# Sheet1.net
KiCad netlist of a schematic drawn in Altium Designer
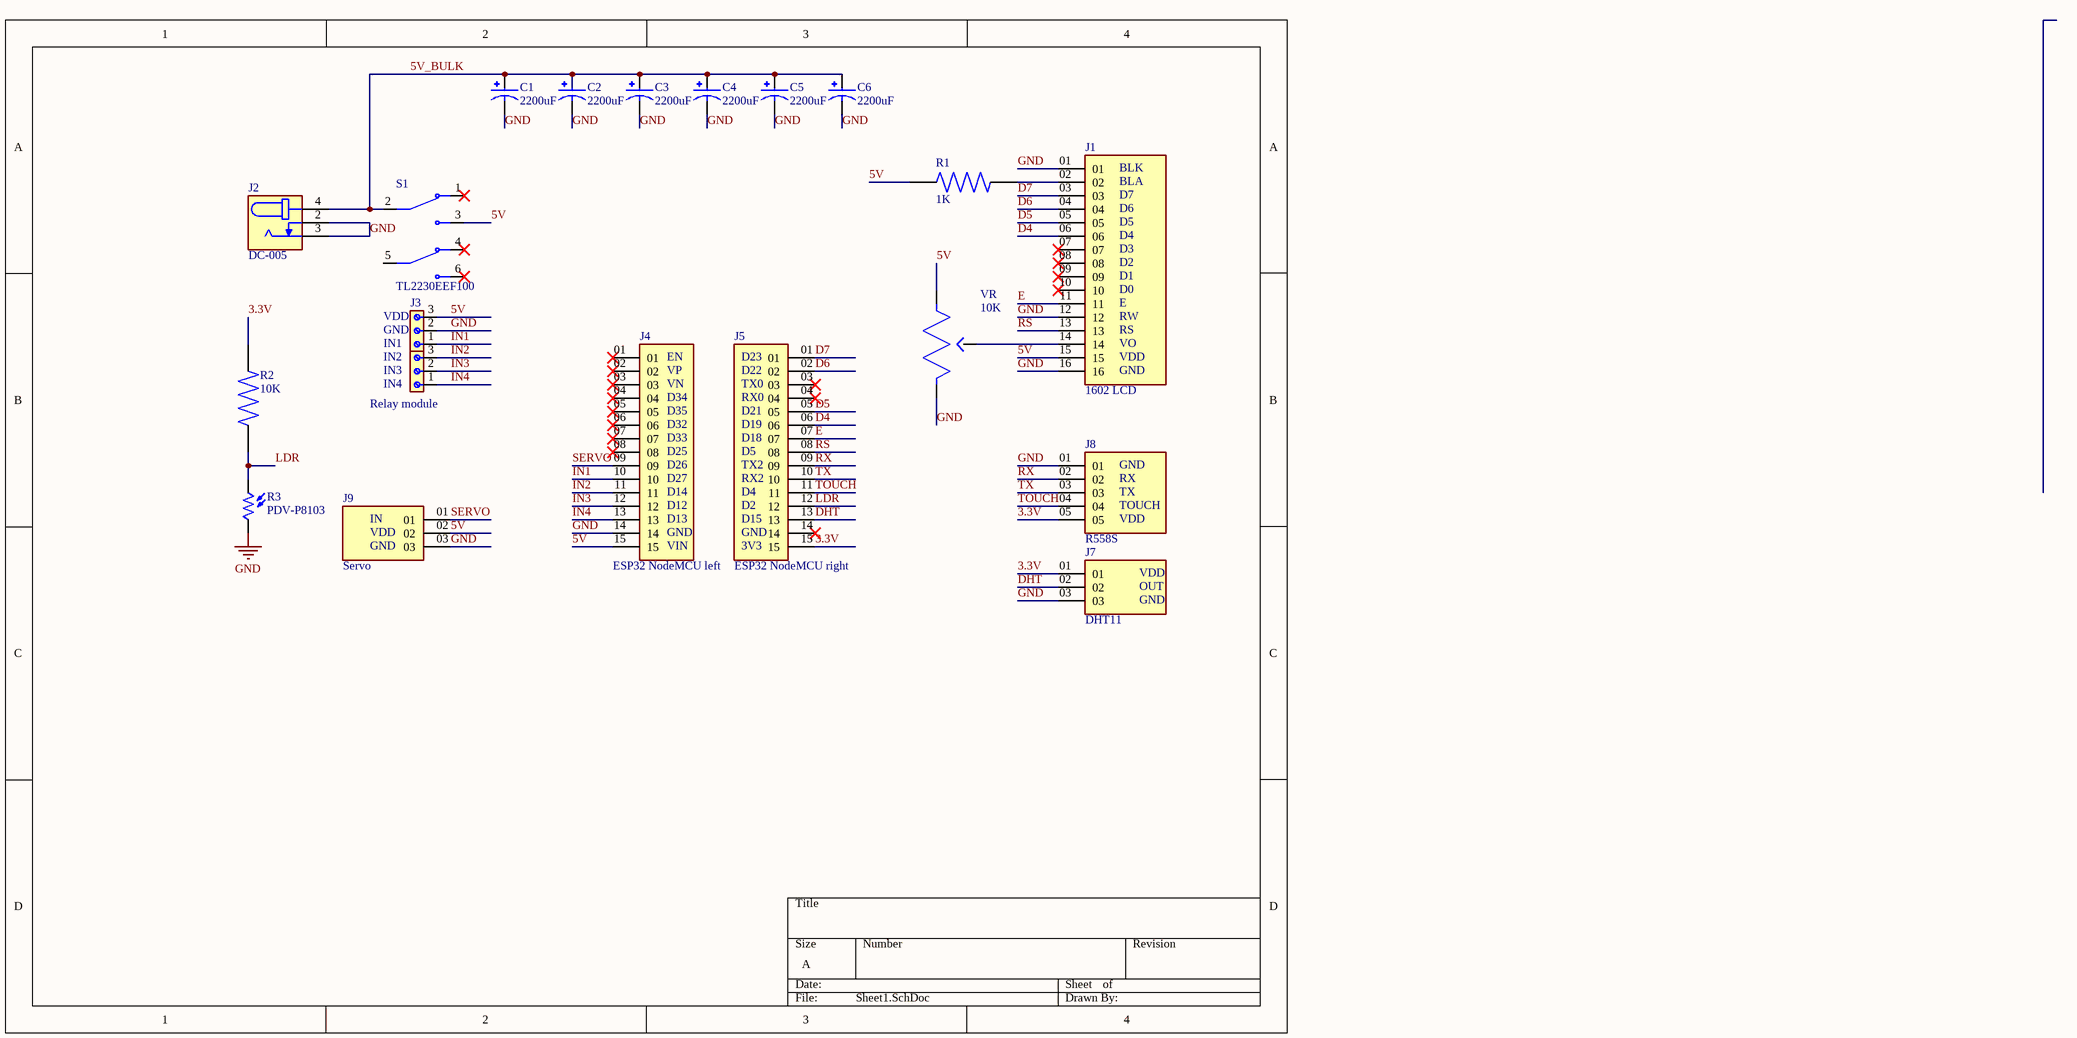
[diagram p0: Sheet1.SchDoc]

(export (version "E")
  (design (tool "Eeschema 10.0.6"))
  (components
    (comp (ref "C1")
      (value "2200uF")
      (footprint "CAPPRD500W60D1250H2000")
      (description "Cap Aluminum Lytic 2200uF 16V 20% (12.5 X 20mm) Radial 5mm 2600mA 10000h 105C Bulk")
      (fields (field (name "MP") "EEUFR1C222") (field (name "MF") "Panasonic"))
      (libsource (lib "EEUFR1C222") (part "EEUFR1C222"))
    )
    (comp (ref "C2")
      (value "2200uF")
      (footprint "CAPPRD500W60D1250H2000")
      (description "Cap Aluminum Lytic 2200uF 16V 20% (12.5 X 20mm) Radial 5mm 2600mA 10000h 105C Bulk")
      (fields (field (name "MP") "EEUFR1C222") (field (name "MF") "Panasonic"))
      (libsource (lib "EEUFR1C222") (part "EEUFR1C222"))
    )
    (comp (ref "C3")
      (value "2200uF")
      (footprint "CAPPRD500W60D1250H2000")
      (description "Cap Aluminum Lytic 2200uF 16V 20% (12.5 X 20mm) Radial 5mm 2600mA 10000h 105C Bulk")
      (fields (field (name "MP") "EEUFR1C222") (field (name "MF") "Panasonic"))
      (libsource (lib "EEUFR1C222") (part "EEUFR1C222"))
    )
    (comp (ref "C4")
      (value "2200uF")
      (footprint "CAPPRD500W60D1250H2000")
      (description "Cap Aluminum Lytic 2200uF 16V 20% (12.5 X 20mm) Radial 5mm 2600mA 10000h 105C Bulk")
      (fields (field (name "MP") "EEUFR1C222") (field (name "MF") "Panasonic"))
      (libsource (lib "EEUFR1C222") (part "EEUFR1C222"))
    )
    (comp (ref "C5")
      (value "2200uF")
      (footprint "CAPPRD500W60D1250H2000")
      (description "Cap Aluminum Lytic 2200uF 16V 20% (12.5 X 20mm) Radial 5mm 2600mA 10000h 105C Bulk")
      (fields (field (name "MP") "EEUFR1C222") (field (name "MF") "Panasonic"))
      (libsource (lib "EEUFR1C222") (part "EEUFR1C222"))
    )
    (comp (ref "C6")
      (value "2200uF")
      (footprint "CAPPRD500W60D1250H2000")
      (description "Cap Aluminum Lytic 2200uF 16V 20% (12.5 X 20mm) Radial 5mm 2600mA 10000h 105C Bulk")
      (fields (field (name "MP") "EEUFR1C222") (field (name "MF") "Panasonic"))
      (libsource (lib "EEUFR1C222") (part "EEUFR1C222"))
    )
    (comp (ref "J1")
      (value "1602 LCD")
      (footprint "SAMTEC_TSW-116-08-F-S")
      (fields (field (name "MP") "TSW-116-08-F-S"))
      (libsource (lib "TSW-116-08-F-S") (part "TSW-116-08-F-S"))
    )
    (comp (ref "J2")
      (value "DC-005")
      (footprint "NINIGI_DC-005")
      (description "DC Jack")
      (libsource (lib "DC-005") (part "DC-005"))
    )
    (comp (ref "J3")
      (value "~")
      (footprint "691213710003")
      (fields (field (name "MF") "Wurth Electronics") (field (name "MP") "691213710003"))
      (libsource (lib "691213710003") (part "691213710003"))
    )
    (comp (ref "J4")
      (value "ESP32 NodeMCU left")
      (footprint "SAMTEC_SSQ-115-X-X-S")
      (description "15 Position Receptacle Connector 0.100 (2.54mm) Through Hole Gold")
      (fields (field (name "MP") "SSQ-115-23-G-S") (field (name "MF") "Samtec"))
      (libsource (lib "SSQ-115-X-X-S") (part "SSQ-115-X-X-S"))
    )
    (comp (ref "J5")
      (value "ESP32 NodeMCU right")
      (footprint "SAMTEC_SSQ-115-X-X-S")
      (description "15 Position Receptacle Connector 0.100 (2.54mm) Through Hole Gold")
      (fields (field (name "MP") "SSQ-115-23-G-S") (field (name "MF") "Samtec"))
      (libsource (lib "") (part "SSQ-115-X-X-S_1"))
    )
    (comp (ref "J6")
      (value "Relay module")
      (footprint "691213710003")
      (fields (field (name "MF") "Wurth Electronics") (field (name "MP") "691213710003"))
      (libsource (lib "691213710003") (part "691213710003"))
    )
    (comp (ref "J7")
      (value "DHT11")
      (footprint "SAMTEC_TSW-103-08-F-S")
      (fields (field (name "MP") "TSW-103-08-F-S"))
      (libsource (lib "") (part "TSW-103-08-F-S_1"))
    )
    (comp (ref "J8")
      (value "R558S")
      (footprint "SAMTEC_MTLW-105-05-G-S-190")
      (fields (field (name "MP") "MTLW-105-05-G-S-190"))
      (libsource (lib "MTLW-105-05-G-S-190") (part "MTLW-105-05-G-S-190"))
    )
    (comp (ref "J9")
      (value "Servo")
      (footprint "SAMTEC_TSW-103-08-F-S")
      (fields (field (name "MP") "TSW-103-08-F-S"))
      (libsource (lib "TSW-103-08-F-S") (part "TSW-103-08-F-S"))
    )
    (comp (ref "R1")
      (value "1K")
      (footprint "RESAD1100W55L680D260")
      (description "1.07 kOhms Â±1% 0.25W, 1/4W Through Hole Resistor Axial - Metal Film")
      (fields (field (name "MF") "Yageo") (field (name "MP") "MFR-25FBF52-1K"))
      (libsource (lib "MFR-25FBF52-1K") (part "MFR-25FBF52-1K"))
    )
    (comp (ref "R2")
      (value "10K")
      (footprint "RESAD1100W55L680D260")
      (description "1.07 kOhms Â±1% 0.25W, 1/4W Through Hole Resistor Axial - Metal Film")
      (fields (field (name "MF") "Yageo") (field (name "MP") "MFR-25FBF52-1K"))
      (libsource (lib "MFR-25FBF52-1K") (part "MFR-25FBF52-1K"))
    )
    (comp (ref "R3")
      (value "PDV-P8103")
      (footprint "PHODET_PDV-P8103")
      (description "CdS Cells 520nm 16 ~ 33kOhms @ 10 lux")
      (fields (field (name "MF") "Advanced Photonix"))
      (libsource (lib "PDV-P8103") (part "PDV-P8103"))
    )
    (comp (ref "S1")
      (value "TL2230EEF100")
      (footprint "SW_TL2230EEF100")
      (description "Pushbutton Switch DPDT Standard Through Hole")
      (fields (field (name "MF") "E-Switch"))
      (libsource (lib "TL2230EEF100") (part "TL2230EEF100"))
    )
    (comp (ref "VR")
      (value "10K")
      (footprint "P160")
      (description "500k Ohm 1 Gang Linear Panel Mount Potentiometer None 1 Turn Conductive Plastic 0.2W, 1/5W PC Pins")
      (fields (field (name "MF") "TT Electronics/BI") (field (name "DIGI-KEY_PART_NUMBER") "987-1304-ND"))
      (libsource (lib "P160KN-0QC15B500K") (part "P160KN-0QC15B500K"))
    )
  )
  (nets
    (net (code "1") (name "/3.3V") (class "Default")
      (node (ref "J5") (pin "15") (pinfunction "15_15") (pintype "passive"))
      (node (ref "J7") (pin "01") (pinfunction "01_01") (pintype "passive"))
      (node (ref "J8") (pin "05") (pinfunction "05_05") (pintype "passive"))
      (node (ref "R2") (pin "1") (pinfunction "1_1") (pintype "passive"))
    )
    (net (code "2") (name "/5V") (class "Default")
      (node (ref "J1") (pin "15") (pinfunction "15_15") (pintype "passive"))
      (node (ref "J3") (pin "3") (pinfunction "3_3") (pintype "passive"))
      (node (ref "J4") (pin "15") (pinfunction "15_15") (pintype "passive"))
      (node (ref "J9") (pin "02") (pinfunction "02_02") (pintype "passive"))
      (node (ref "R1") (pin "1") (pinfunction "1_1") (pintype "passive"))
      (node (ref "S1") (pin "3") (pinfunction "NO1_3") (pintype "passive"))
      (node (ref "VR") (pin "3") (pinfunction "3_3") (pintype "bidirectional"))
    )
    (net (code "3") (name "/5V_BULK") (class "Default")
      (node (ref "C1") (pin "P") (pinfunction "P_P") (pintype "passive"))
      (node (ref "C2") (pin "P") (pinfunction "P_P") (pintype "passive"))
      (node (ref "C3") (pin "P") (pinfunction "P_P") (pintype "passive"))
      (node (ref "C4") (pin "P") (pinfunction "P_P") (pintype "passive"))
      (node (ref "C5") (pin "P") (pinfunction "P_P") (pintype "passive"))
      (node (ref "C6") (pin "P") (pinfunction "P_P") (pintype "passive"))
      (node (ref "J2") (pin "4") (pinfunction "2_4") (pintype "passive"))
      (node (ref "S1") (pin "2") (pinfunction "COM1_2") (pintype "passive"))
    )
    (net (code "4") (name "/D4") (class "Default")
      (node (ref "J1") (pin "06") (pinfunction "06_06") (pintype "passive"))
      (node (ref "J5") (pin "06") (pinfunction "06_06") (pintype "passive"))
    )
    (net (code "5") (name "/D5") (class "Default")
      (node (ref "J1") (pin "05") (pinfunction "05_05") (pintype "passive"))
      (node (ref "J5") (pin "05") (pinfunction "05_05") (pintype "passive"))
    )
    (net (code "6") (name "/D6") (class "Default")
      (node (ref "J1") (pin "04") (pinfunction "04_04") (pintype "passive"))
      (node (ref "J5") (pin "02") (pinfunction "02_02") (pintype "passive"))
    )
    (net (code "7") (name "/D7") (class "Default")
      (node (ref "J1") (pin "03") (pinfunction "03_03") (pintype "passive"))
      (node (ref "J5") (pin "01") (pinfunction "01_01") (pintype "passive"))
    )
    (net (code "8") (name "/DHT") (class "Default")
      (node (ref "J5") (pin "13") (pinfunction "13_13") (pintype "passive"))
      (node (ref "J7") (pin "02") (pinfunction "02_02") (pintype "passive"))
    )
    (net (code "9") (name "/E") (class "Default")
      (node (ref "J1") (pin "11") (pinfunction "11_11") (pintype "passive"))
      (node (ref "J5") (pin "07") (pinfunction "07_07") (pintype "passive"))
    )
    (net (code "10") (name "/IN1") (class "Default")
      (node (ref "J3") (pin "1") (pinfunction "1_1") (pintype "passive"))
      (node (ref "J4") (pin "10") (pinfunction "10_10") (pintype "passive"))
    )
    (net (code "11") (name "/IN2") (class "Default")
      (node (ref "J4") (pin "11") (pinfunction "11_11") (pintype "passive"))
      (node (ref "J6") (pin "3") (pinfunction "3_3") (pintype "passive"))
    )
    (net (code "12") (name "/IN3") (class "Default")
      (node (ref "J4") (pin "12") (pinfunction "12_12") (pintype "passive"))
      (node (ref "J6") (pin "2") (pinfunction "2_2") (pintype "passive"))
    )
    (net (code "13") (name "/IN4") (class "Default")
      (node (ref "J4") (pin "13") (pinfunction "13_13") (pintype "passive"))
      (node (ref "J6") (pin "1") (pinfunction "1_1") (pintype "passive"))
    )
    (net (code "14") (name "/LDR") (class "Default")
      (node (ref "J5") (pin "12") (pinfunction "12_12") (pintype "passive"))
      (node (ref "R2") (pin "2") (pinfunction "2_2") (pintype "passive"))
      (node (ref "R3") (pin "1") (pinfunction "1_1") (pintype "passive"))
    )
    (net (code "15") (name "/RS") (class "Default")
      (node (ref "J1") (pin "13") (pinfunction "13_13") (pintype "passive"))
      (node (ref "J5") (pin "08") (pinfunction "08_08") (pintype "passive"))
    )
    (net (code "16") (name "/RX") (class "Default")
      (node (ref "J5") (pin "09") (pinfunction "09_09") (pintype "passive"))
      (node (ref "J8") (pin "02") (pinfunction "02_02") (pintype "passive"))
    )
    (net (code "17") (name "/SERVO") (class "Default")
      (node (ref "J4") (pin "09") (pinfunction "09_09") (pintype "passive"))
      (node (ref "J9") (pin "01") (pinfunction "01_01") (pintype "passive"))
    )
    (net (code "18") (name "/TOUCH") (class "Default")
      (node (ref "J5") (pin "11") (pinfunction "11_11") (pintype "passive"))
      (node (ref "J8") (pin "04") (pinfunction "04_04") (pintype "passive"))
    )
    (net (code "19") (name "/TX") (class "Default")
      (node (ref "J5") (pin "10") (pinfunction "10_10") (pintype "passive"))
      (node (ref "J8") (pin "03") (pinfunction "03_03") (pintype "passive"))
    )
    (net (code "20") (name "GND") (class "Default")
      (node (ref "C1") (pin "N") (pinfunction "N_N") (pintype "passive"))
      (node (ref "C2") (pin "N") (pinfunction "N_N") (pintype "passive"))
      (node (ref "C3") (pin "N") (pinfunction "N_N") (pintype "passive"))
      (node (ref "C4") (pin "N") (pinfunction "N_N") (pintype "passive"))
      (node (ref "C5") (pin "N") (pinfunction "N_N") (pintype "passive"))
      (node (ref "C6") (pin "N") (pinfunction "N_N") (pintype "passive"))
      (node (ref "J1") (pin "01") (pinfunction "01_01") (pintype "passive"))
      (node (ref "J1") (pin "12") (pinfunction "12_12") (pintype "passive"))
      (node (ref "J1") (pin "16") (pinfunction "16_16") (pintype "passive"))
      (node (ref "J2") (pin "2") (pinfunction "4_2") (pintype "passive"))
      (node (ref "J2") (pin "3") (pinfunction "5_3") (pintype "passive"))
      (node (ref "J3") (pin "2") (pinfunction "2_2") (pintype "passive"))
      (node (ref "J4") (pin "14") (pinfunction "14_14") (pintype "passive"))
      (node (ref "J7") (pin "03") (pinfunction "03_03") (pintype "passive"))
      (node (ref "J8") (pin "01") (pinfunction "01_01") (pintype "passive"))
      (node (ref "J9") (pin "03") (pinfunction "03_03") (pintype "passive"))
      (node (ref "R3") (pin "2") (pinfunction "2_2") (pintype "passive"))
      (node (ref "VR") (pin "1") (pinfunction "1_1") (pintype "bidirectional"))
    )
    (net (code "21") (name "Net-(J1-Pad02)") (class "Default")
      (node (ref "J1") (pin "02") (pinfunction "02_02") (pintype "passive"))
      (node (ref "R1") (pin "2") (pinfunction "2_2") (pintype "passive"))
    )
    (net (code "22") (name "Net-(J1-Pad14)") (class "Default")
      (node (ref "J1") (pin "14") (pinfunction "14_14") (pintype "passive"))
      (node (ref "VR") (pin "2") (pinfunction "2_2") (pintype "bidirectional"))
    )
    (net (code "23") (name "unconnected-(J1-Pad07)") (class "Default")
      (node (ref "J1") (pin "07") (pinfunction "07_07") (pintype "passive+no_connect"))
    )
    (net (code "24") (name "unconnected-(J1-Pad08)") (class "Default")
      (node (ref "J1") (pin "08") (pinfunction "08_08") (pintype "passive+no_connect"))
    )
    (net (code "25") (name "unconnected-(J1-Pad09)") (class "Default")
      (node (ref "J1") (pin "09") (pinfunction "09_09") (pintype "passive+no_connect"))
    )
    (net (code "26") (name "unconnected-(J1-Pad10)") (class "Default")
      (node (ref "J1") (pin "10") (pinfunction "10_10") (pintype "passive+no_connect"))
    )
    (net (code "27") (name "unconnected-(J4-Pad01)") (class "Default")
      (node (ref "J4") (pin "01") (pinfunction "01_01") (pintype "passive+no_connect"))
    )
    (net (code "28") (name "unconnected-(J4-Pad02)") (class "Default")
      (node (ref "J4") (pin "02") (pinfunction "02_02") (pintype "passive+no_connect"))
    )
    (net (code "29") (name "unconnected-(J4-Pad03)") (class "Default")
      (node (ref "J4") (pin "03") (pinfunction "03_03") (pintype "passive+no_connect"))
    )
    (net (code "30") (name "unconnected-(J4-Pad04)") (class "Default")
      (node (ref "J4") (pin "04") (pinfunction "04_04") (pintype "passive+no_connect"))
    )
    (net (code "31") (name "unconnected-(J4-Pad05)") (class "Default")
      (node (ref "J4") (pin "05") (pinfunction "05_05") (pintype "passive+no_connect"))
    )
    (net (code "32") (name "unconnected-(J4-Pad06)") (class "Default")
      (node (ref "J4") (pin "06") (pinfunction "06_06") (pintype "passive+no_connect"))
    )
    (net (code "33") (name "unconnected-(J4-Pad07)") (class "Default")
      (node (ref "J4") (pin "07") (pinfunction "07_07") (pintype "passive+no_connect"))
    )
    (net (code "34") (name "unconnected-(J4-Pad08)") (class "Default")
      (node (ref "J4") (pin "08") (pinfunction "08_08") (pintype "passive+no_connect"))
    )
    (net (code "35") (name "unconnected-(J5-Pad03)") (class "Default")
      (node (ref "J5") (pin "03") (pinfunction "03_03") (pintype "passive+no_connect"))
    )
    (net (code "36") (name "unconnected-(J5-Pad04)") (class "Default")
      (node (ref "J5") (pin "04") (pinfunction "04_04") (pintype "passive+no_connect"))
    )
    (net (code "37") (name "unconnected-(J5-Pad14)") (class "Default")
      (node (ref "J5") (pin "14") (pinfunction "14_14") (pintype "passive+no_connect"))
    )
    (net (code "38") (name "unconnected-(S1-COM2-Pad5)") (class "Default")
      (node (ref "S1") (pin "5") (pinfunction "COM2_5") (pintype "passive"))
    )
    (net (code "39") (name "unconnected-(S1-NC1-Pad1)") (class "Default")
      (node (ref "S1") (pin "1") (pinfunction "NC1_1") (pintype "passive+no_connect"))
    )
    (net (code "40") (name "unconnected-(S1-NC2-Pad4)") (class "Default")
      (node (ref "S1") (pin "4") (pinfunction "NC2_4") (pintype "passive+no_connect"))
    )
    (net (code "41") (name "unconnected-(S1-NO2-Pad6)") (class "Default")
      (node (ref "S1") (pin "6") (pinfunction "NO2_6") (pintype "passive+no_connect"))
    )
  )
)
